# UNG8077_EVB_7801-9031_A_4-KSZ9031.net
KiCad netlist of a schematic drawn in Altium Designer
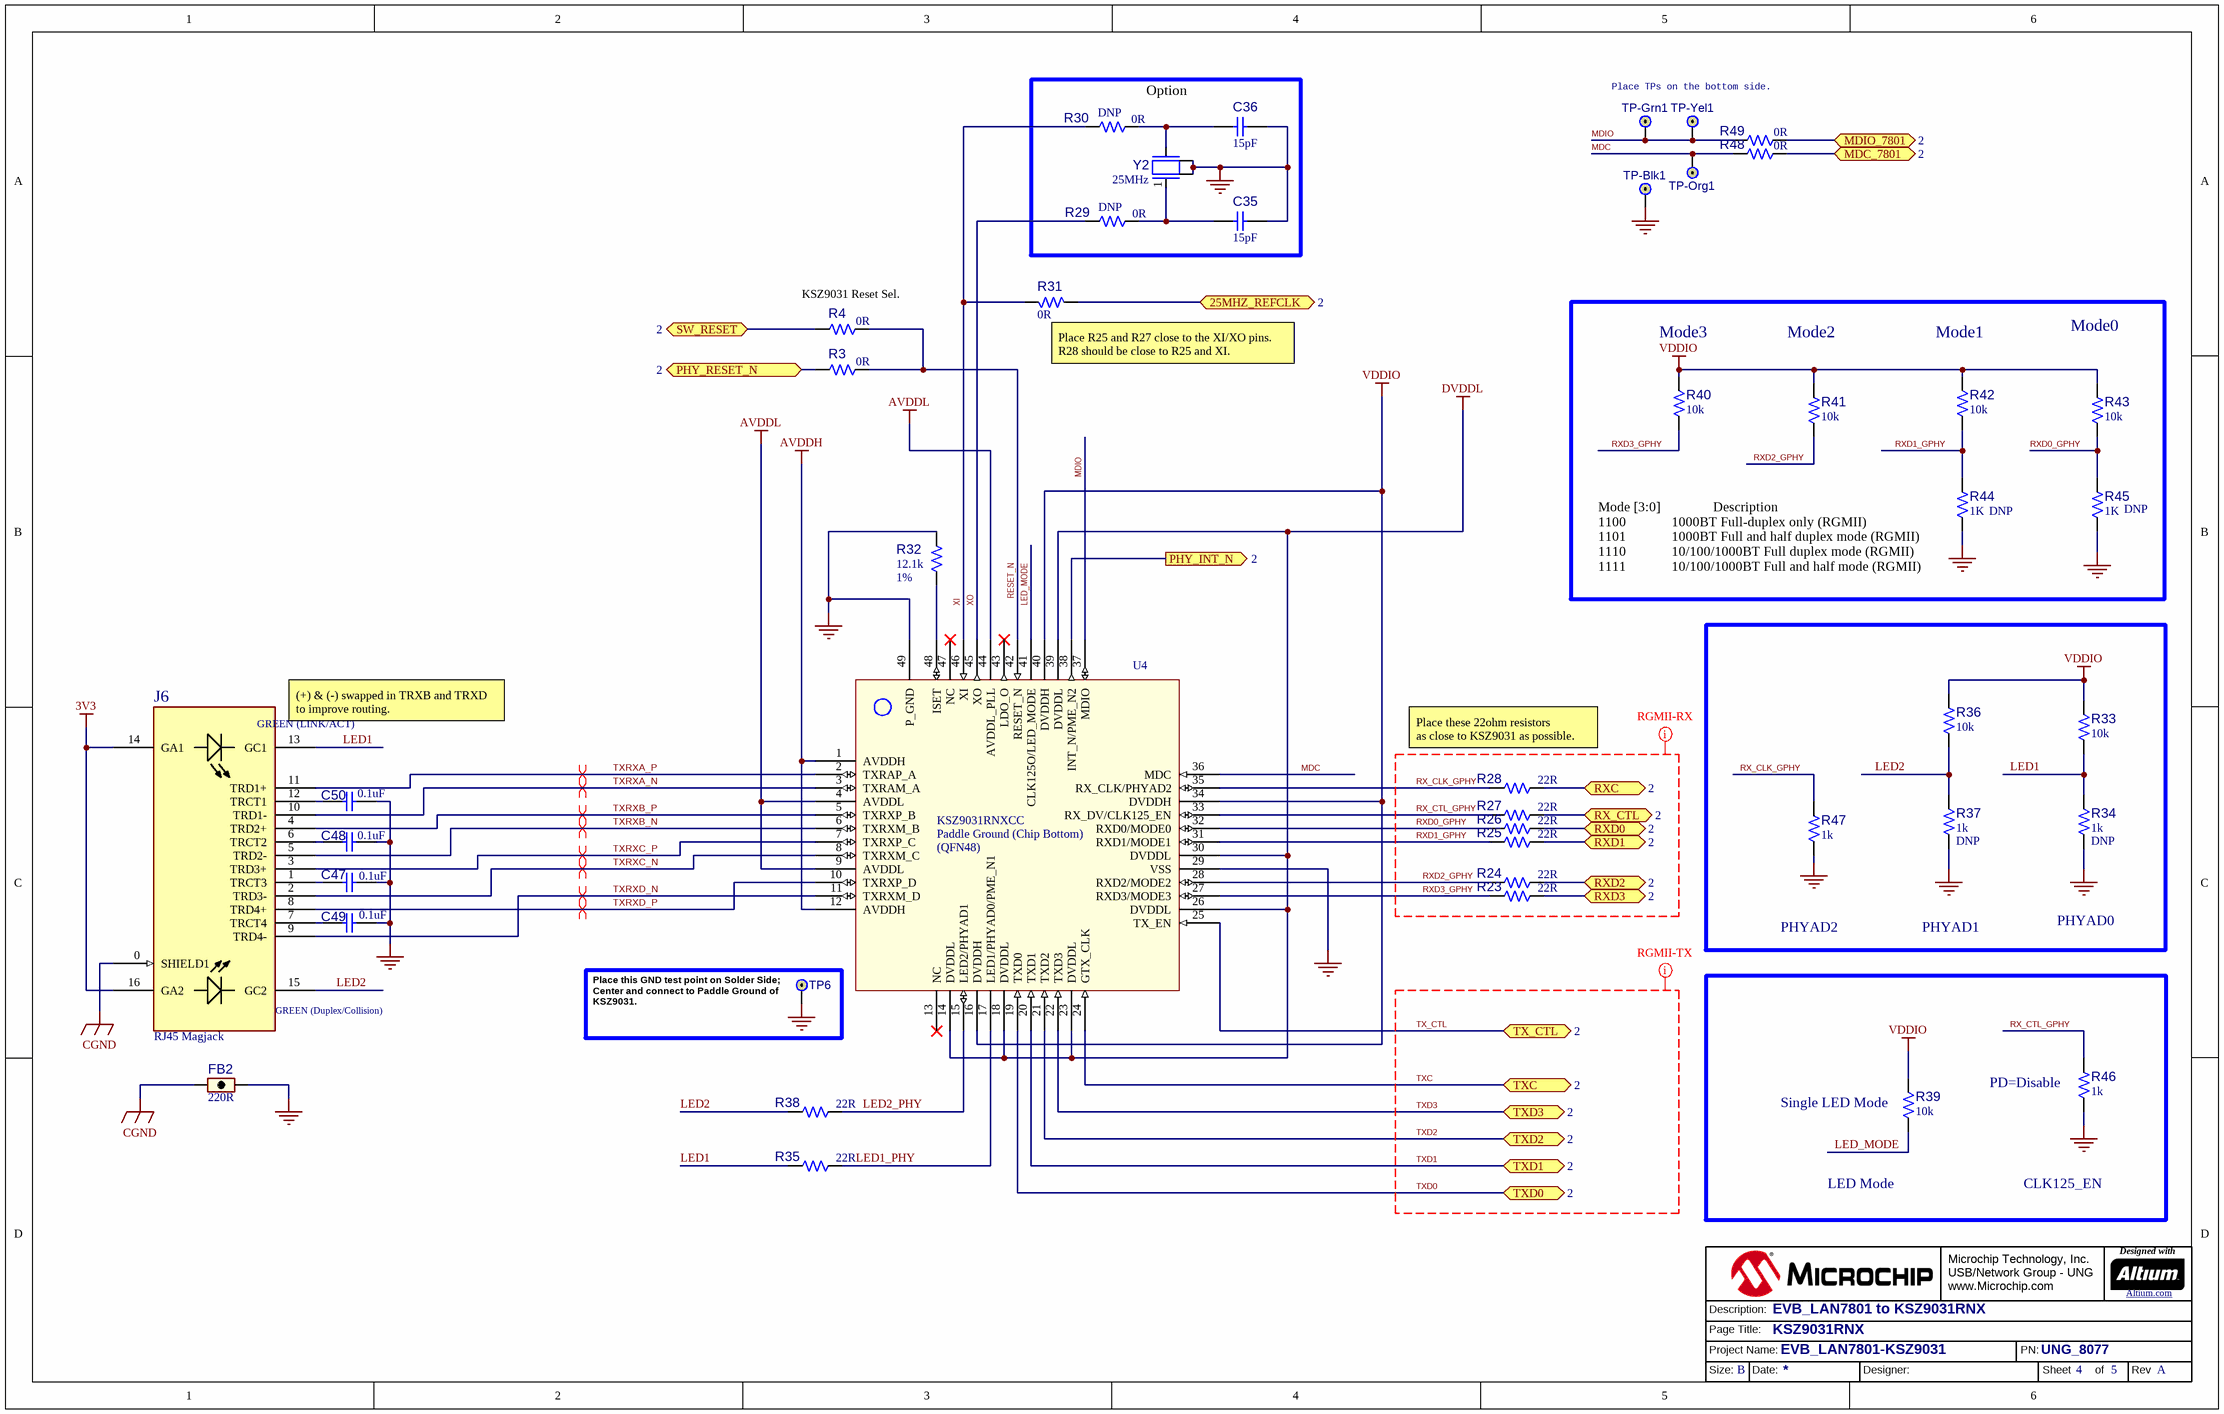
[diagram p0: UNG8077_EVB_7801-9031_A_4-KSZ9031.SchDoc]

(export (version "E")
  (design (tool "Eeschema 10.0.6"))
  (components
    (comp (ref "C35")
      (value "15pF")
      (footprint "CAP_C_0402")
      (description "Capacitor")
      (fields
        (field (name "TOLERANCE") "5%")
        (field (name "Comment") "Capacitor NP")
        (field (name "OWNER") "Gabor Bihari")
      )
      (libsource (lib "MCHP-CDB-Offline") (part "Capacitor NP"))
    )
    (comp (ref "C36")
      (value "15pF")
      (footprint "CAP_C_0402")
      (description "Capacitor")
      (fields
        (field (name "TOLERANCE") "5%")
        (field (name "Comment") "Capacitor NP")
        (field (name "OWNER") "Gabor Bihari")
      )
      (libsource (lib "MCHP-CDB-Offline") (part "Capacitor NP"))
    )
    (comp (ref "C47")
      (value "0.1uF")
      (footprint "CAP_C_0402")
      (description "Capacitor")
      (fields
        (field (name "TOLERANCE") "10%")
        (field (name "Comment") "CAP CER 0.1UF 35V")
        (field (name "OWNER") "Jamus Griego")
      )
      (libsource (lib "MCHP-CDB-Offline") (part "Capacitor NP"))
    )
    (comp (ref "C48")
      (value "0.1uF")
      (footprint "CAP_C_0402")
      (description "Capacitor")
      (fields
        (field (name "TOLERANCE") "10%")
        (field (name "Comment") "CAP CER 0.1UF 35V")
        (field (name "OWNER") "Jamus Griego")
      )
      (libsource (lib "MCHP-CDB-Offline") (part "Capacitor NP"))
    )
    (comp (ref "C49")
      (value "0.1uF")
      (footprint "CAP_C_0402")
      (description "Capacitor")
      (fields
        (field (name "TOLERANCE") "10%")
        (field (name "Comment") "CAP CER 0.1UF 35V")
        (field (name "OWNER") "Jamus Griego")
      )
      (libsource (lib "MCHP-CDB-Offline") (part "Capacitor NP"))
    )
    (comp (ref "C50")
      (value "0.1uF")
      (footprint "CAP_C_0402")
      (description "Capacitor")
      (fields
        (field (name "TOLERANCE") "10%")
        (field (name "Comment") "CAP CER 0.1UF 35V")
        (field (name "OWNER") "Jamus Griego")
      )
      (libsource (lib "MCHP-CDB-Offline") (part "Capacitor NP"))
    )
    (comp (ref "FB2")
      (value "220R")
      (footprint "IND_C_0603")
      (fields (field (name "Comment") "Ferrite Bead") (field (name "OWNER") "Razvan Cristescu"))
      (libsource (lib "MCHP-CDB-Offline") (part "Ferrite Bead"))
    )
    (comp (ref "J6")
      (value "RJ45 Magjack")
      (footprint "CON_MODULAR_RJ45_TH_RA_RJMG2012211A0FR")
      (description "CON RJ-45 RJMG2012211A0FR")
      (libsource (lib "UNG_CONNECTORS") (part "CON RJ-45 RJMG2012211A0FR"))
    )
    (comp (ref "R3")
      (value "0R")
      (footprint "RES_C_0603")
      (description "Resistor")
      (fields (field (name "POWER") "1/10W"))
      (libsource (lib "MCHP-CDB-Offline") (part "Resistor"))
    )
    (comp (ref "R4")
      (value "0R")
      (footprint "RES_C_0603")
      (description "Resistor")
      (fields (field (name "POWER") "1/10W"))
      (libsource (lib "MCHP-CDB-Offline") (part "Resistor"))
    )
    (comp (ref "R23")
      (value "22R")
      (footprint "RES_C_0402")
      (description "Resistor")
      (fields
        (field (name "TOLERANCE") "1%")
        (field (name "POWER") "1/10W")
        (field (name "OWNER") "Mike Ragsdale")
      )
      (libsource (lib "MCHP-CDB") (part "Resistor"))
    )
    (comp (ref "R24")
      (value "22R")
      (footprint "RES_C_0402")
      (description "Resistor")
      (fields
        (field (name "TOLERANCE") "1%")
        (field (name "POWER") "1/10W")
        (field (name "OWNER") "Mike Ragsdale")
      )
      (libsource (lib "MCHP-CDB") (part "Resistor"))
    )
    (comp (ref "R25")
      (value "22R")
      (footprint "RES_C_0402")
      (description "Resistor")
      (fields
        (field (name "TOLERANCE") "1%")
        (field (name "POWER") "1/10W")
        (field (name "OWNER") "Mike Ragsdale")
      )
      (libsource (lib "MCHP-CDB") (part "Resistor"))
    )
    (comp (ref "R26")
      (value "22R")
      (footprint "RES_C_0402")
      (description "Resistor")
      (fields
        (field (name "TOLERANCE") "1%")
        (field (name "POWER") "1/10W")
        (field (name "OWNER") "Mike Ragsdale")
      )
      (libsource (lib "MCHP-CDB") (part "Resistor"))
    )
    (comp (ref "R27")
      (value "22R")
      (footprint "RES_C_0402")
      (description "Resistor")
      (fields
        (field (name "TOLERANCE") "1%")
        (field (name "POWER") "1/10W")
        (field (name "OWNER") "Mike Ragsdale")
      )
      (libsource (lib "MCHP-CDB") (part "Resistor"))
    )
    (comp (ref "R28")
      (value "22R")
      (footprint "RES_C_0402")
      (description "Resistor")
      (fields
        (field (name "TOLERANCE") "1%")
        (field (name "POWER") "1/10W")
        (field (name "OWNER") "Mike Ragsdale")
      )
      (libsource (lib "MCHP-CDB") (part "Resistor"))
    )
    (comp (ref "R29")
      (value "0R")
      (footprint "RES_C_0603")
      (description "Resistor")
      (fields (field (name "POWER") "1/10W") (field (name "POPULATED") "DNP"))
      (libsource (lib "MCHP-CDB-Offline") (part "Resistor"))
    )
    (comp (ref "R30")
      (value "0R")
      (footprint "RES_C_0603")
      (description "Resistor")
      (fields (field (name "POWER") "1/10W") (field (name "POPULATED") "DNP"))
      (libsource (lib "MCHP-CDB-Offline") (part "Resistor"))
    )
    (comp (ref "R31")
      (value "0R")
      (footprint "RES_C_0603")
      (description "Resistor")
      (fields (field (name "POWER") "1/10W"))
      (libsource (lib "MCHP-CDB-Offline") (part "Resistor"))
    )
    (comp (ref "R32")
      (value "12.1k")
      (footprint "RES_C_0603")
      (description "Resistor")
      (fields (field (name "TOLERANCE") "1%") (field (name "VOLTAGE") "75V") (field (name "POWER") "1/10W"))
      (libsource (lib "MCHP-CDB-Offline") (part "Resistor"))
    )
    (comp (ref "R33")
      (value "10k")
      (footprint "RES_C_0603")
      (description "Resistor")
      (fields (field (name "VOLTAGE") "75V") (field (name "POWER") "1/10W"))
      (libsource (lib "MCHP-CDB-Offline") (part "Resistor"))
    )
    (comp (ref "R34")
      (value "1k")
      (footprint "RES_C_0603")
      (description "Resistor")
      (fields (field (name "TOLERANCE") "1%") (field (name "VOLTAGE") "75V") (field (name "POPULATED") "DNP"))
      (libsource (lib "MCHP-CDB") (part "Resistor"))
    )
    (comp (ref "R35")
      (value "22R")
      (footprint "RES_C_0402")
      (description "Resistor")
      (fields
        (field (name "TOLERANCE") "1%")
        (field (name "POWER") "1/10W")
        (field (name "OWNER") "Mike Ragsdale")
      )
      (libsource (lib "MCHP-CDB") (part "Resistor"))
    )
    (comp (ref "R36")
      (value "10k")
      (footprint "RES_C_0603")
      (description "Resistor")
      (fields (field (name "VOLTAGE") "75V") (field (name "POWER") "1/10W"))
      (libsource (lib "MCHP-CDB-Offline") (part "Resistor"))
    )
    (comp (ref "R37")
      (value "1k")
      (footprint "RES_C_0603")
      (description "Resistor")
      (fields (field (name "TOLERANCE") "1%") (field (name "VOLTAGE") "75V") (field (name "POPULATED") "DNP"))
      (libsource (lib "MCHP-CDB") (part "Resistor"))
    )
    (comp (ref "R38")
      (value "22R")
      (footprint "RES_C_0402")
      (description "Resistor")
      (fields
        (field (name "TOLERANCE") "1%")
        (field (name "POWER") "1/10W")
        (field (name "OWNER") "Mike Ragsdale")
      )
      (libsource (lib "MCHP-CDB") (part "Resistor"))
    )
    (comp (ref "R39")
      (value "10k")
      (footprint "RES_C_0603")
      (description "Resistor")
      (fields (field (name "VOLTAGE") "75V") (field (name "POWER") "1/10W"))
      (libsource (lib "MCHP-CDB-Offline") (part "Resistor"))
    )
    (comp (ref "R40")
      (value "10k")
      (footprint "RES_C_0603")
      (description "Resistor")
      (fields (field (name "VOLTAGE") "75V") (field (name "POWER") "1/10W"))
      (libsource (lib "MCHP-CDB-Offline") (part "Resistor"))
    )
    (comp (ref "R41")
      (value "10k")
      (footprint "RES_C_0603")
      (description "Resistor")
      (fields (field (name "VOLTAGE") "75V") (field (name "POWER") "1/10W"))
      (libsource (lib "MCHP-CDB-Offline") (part "Resistor"))
    )
    (comp (ref "R42")
      (value "10k")
      (footprint "RES_C_0603")
      (description "Resistor")
      (fields (field (name "VOLTAGE") "75V") (field (name "POWER") "1/10W"))
      (libsource (lib "MCHP-CDB-Offline") (part "Resistor"))
    )
    (comp (ref "R43")
      (value "10k")
      (footprint "RES_C_0603")
      (description "Resistor")
      (fields (field (name "VOLTAGE") "75V") (field (name "POWER") "1/10W"))
      (libsource (lib "MCHP-CDB-Offline") (part "Resistor"))
    )
    (comp (ref "R44")
      (value "1K")
      (footprint "RES_C_0603")
      (description "Resistor")
      (fields (field (name "TOLERANCE") "5%") (field (name "VOLTAGE") "75V") (field (name "POPULATED") "DNP"))
      (libsource (lib "MCHP-CDB-Offline") (part "Resistor"))
    )
    (comp (ref "R45")
      (value "1K")
      (footprint "RES_C_0603")
      (description "Resistor")
      (fields (field (name "TOLERANCE") "5%") (field (name "VOLTAGE") "75V") (field (name "POPULATED") "DNP"))
      (libsource (lib "MCHP-CDB-Offline") (part "Resistor"))
    )
    (comp (ref "R46")
      (value "1k")
      (footprint "RES_C_0603")
      (description "Resistor")
      (fields (field (name "TOLERANCE") "1%") (field (name "VOLTAGE") "75V"))
      (libsource (lib "MCHP-CDB") (part "Resistor"))
    )
    (comp (ref "R47")
      (value "1k")
      (footprint "RES_C_0603")
      (description "Resistor")
      (fields (field (name "TOLERANCE") "1%") (field (name "VOLTAGE") "75V"))
      (libsource (lib "MCHP-CDB") (part "Resistor"))
    )
    (comp (ref "R48")
      (value "0R")
      (footprint "RES_C_0603")
      (description "Resistor")
      (fields (field (name "POWER") "1/10W"))
      (libsource (lib "MCHP-CDB-Offline") (part "Resistor"))
    )
    (comp (ref "R49")
      (value "0R")
      (footprint "RES_C_0603")
      (description "Resistor")
      (fields (field (name "POWER") "1/10W"))
      (libsource (lib "MCHP-CDB-Offline") (part "Resistor"))
    )
    (comp (ref "TP-Blk1")
      (value "Jumper")
      (footprint "TP_PAD51D36")
      (description "Test Pad TH 51X36")
      (fields (field (name "MANUFACTURER PART NUMBER") "none"))
      (libsource (lib "UNG_CONNECTORS") (part "TEST PAD TH 51X36"))
    )
    (comp (ref "TP-Grn1")
      (value "Jumper")
      (footprint "TP_PAD51D36")
      (description "Test Pad TH 51X36")
      (fields (field (name "MANUFACTURER PART NUMBER") "none"))
      (libsource (lib "UNG_CONNECTORS") (part "TEST PAD TH 51X36"))
    )
    (comp (ref "TP-Org1")
      (value "Jumper")
      (footprint "TP_PAD51D36")
      (description "Test Pad TH 51X36")
      (fields (field (name "MANUFACTURER PART NUMBER") "none"))
      (libsource (lib "UNG_CONNECTORS") (part "TEST PAD TH 51X36"))
    )
    (comp (ref "TP-Yel1")
      (value "Jumper")
      (footprint "TP_PAD51D36")
      (description "Test Pad TH 51X36")
      (fields (field (name "MANUFACTURER PART NUMBER") "none"))
      (libsource (lib "UNG_CONNECTORS") (part "TEST PAD TH 51X36"))
    )
    (comp (ref "TP6")
      (value "Jumper")
      (footprint "TP_PAD_VIA_20-10")
      (description "Test Pad TH VIA 20X10")
      (fields (field (name "MANUFACTURER PART NUMBER") "none"))
      (libsource (lib "UNG_CONNECTORS") (part "TEST PAD TH VIA 20X10"))
    )
    (comp (ref "U4")
      (value "~")
      (footprint "QFN-48_7x7-EP5.1sq")
      (description "KSZ9031RNXCC 10/100/100 GPHY with RGMII 48QFN")
      (fields
        (field (name "OWNER") "Jennifer Hancock")
        (field (name "PART CHECKED") "Jennifer Hancock")
        (field (name "PART FOOTPRINT CHECKED") "Carl Johnson")
      )
      (libsource (lib "UNG_UNG") (part "KSZ9031RNXCC"))
    )
    (comp (ref "Y2")
      (value "XTAL 25MHz 4 pins 3225")
      (footprint "XTAL_4PIN_3M2X2M5")
      (description "Crystal 25MHz 4 pins 3225")
      (fields (field (name "FREQUENCY") "25MHz"))
      (libsource (lib "UNG_XTAL_OSC") (part "XTAL 25MHz 4 pins 3225"))
    )
  )
  (nets
    (net (code "1") (name "/25MHZ_REFCLK") (class "Default")
      (node (ref "R31") (pin "1") (pinfunction "1_1") (pintype "passive"))
    )
    (net (code "2") (name "/LED1") (class "Default")
      (node (ref "J6") (pin "13") (pinfunction "GC1_13") (pintype "passive"))
      (node (ref "R33") (pin "2") (pinfunction "2_2") (pintype "passive"))
      (node (ref "R34") (pin "2") (pinfunction "2_2") (pintype "passive"))
      (node (ref "R35") (pin "1") (pinfunction "1_1") (pintype "passive"))
    )
    (net (code "3") (name "/LED1_PHY") (class "Default")
      (node (ref "R35") (pin "2") (pinfunction "2_2") (pintype "passive"))
      (node (ref "U4") (pin "17") (pinfunction "LED1/PHYAD0/PME_N1_17") (pintype "passive"))
    )
    (net (code "4") (name "/LED2") (class "Default")
      (node (ref "J6") (pin "15") (pinfunction "GC2_15") (pintype "passive"))
      (node (ref "R36") (pin "2") (pinfunction "2_2") (pintype "passive"))
      (node (ref "R37") (pin "2") (pinfunction "2_2") (pintype "passive"))
      (node (ref "R38") (pin "1") (pinfunction "1_1") (pintype "passive"))
    )
    (net (code "5") (name "/LED2_PHY") (class "Default")
      (node (ref "R38") (pin "2") (pinfunction "2_2") (pintype "passive"))
      (node (ref "U4") (pin "15") (pinfunction "LED2/PHYAD1_15") (pintype "bidirectional"))
    )
    (net (code "6") (name "/LED_MODE") (class "Default")
      (node (ref "R39") (pin "2") (pinfunction "2_2") (pintype "passive"))
      (node (ref "U4") (pin "41") (pinfunction "CLK125O/LED_MODE_41") (pintype "passive"))
    )
    (net (code "7") (name "/MDC") (class "Default")
      (node (ref "R48") (pin "1") (pinfunction "1_1") (pintype "passive"))
      (node (ref "TP-Org1") (pin "1") (pinfunction "P1_1") (pintype "passive"))
      (node (ref "U4") (pin "36") (pinfunction "MDC_36") (pintype "input"))
    )
    (net (code "8") (name "/MDC_7801") (class "Default")
      (node (ref "R48") (pin "2") (pinfunction "2_2") (pintype "passive"))
    )
    (net (code "9") (name "/MDIO") (class "Default")
      (node (ref "R49") (pin "1") (pinfunction "1_1") (pintype "passive"))
      (node (ref "TP-Grn1") (pin "1") (pinfunction "P1_1") (pintype "passive"))
      (node (ref "TP-Yel1") (pin "1") (pinfunction "P1_1") (pintype "passive"))
      (node (ref "U4") (pin "37") (pinfunction "MDIO_37") (pintype "bidirectional"))
    )
    (net (code "10") (name "/MDIO_7801") (class "Default")
      (node (ref "R49") (pin "2") (pinfunction "2_2") (pintype "passive"))
    )
    (net (code "11") (name "/PHY_INT_N") (class "Default")
      (node (ref "U4") (pin "38") (pinfunction "INT_N/PME_N2_38") (pintype "output"))
    )
    (net (code "12") (name "/PHY_RESET_N") (class "Default")
      (node (ref "R3") (pin "1") (pinfunction "1_1") (pintype "passive"))
    )
    (net (code "13") (name "/RESET_N") (class "Default")
      (node (ref "R3") (pin "2") (pinfunction "2_2") (pintype "passive"))
      (node (ref "R4") (pin "2") (pinfunction "2_2") (pintype "passive"))
      (node (ref "U4") (pin "42") (pinfunction "RESET_N_42") (pintype "input"))
    )
    (net (code "14") (name "/RXC") (class "Default")
      (node (ref "R28") (pin "2") (pinfunction "2_2") (pintype "passive"))
    )
    (net (code "15") (name "/RXD0") (class "Default")
      (node (ref "R26") (pin "2") (pinfunction "2_2") (pintype "passive"))
    )
    (net (code "16") (name "/RXD0_GPHY") (class "Default")
      (node (ref "R26") (pin "1") (pinfunction "1_1") (pintype "passive"))
      (node (ref "R43") (pin "2") (pinfunction "2_2") (pintype "passive"))
      (node (ref "R45") (pin "2") (pinfunction "2_2") (pintype "passive"))
      (node (ref "U4") (pin "32") (pinfunction "RXD0/MODE0_32") (pintype "bidirectional"))
    )
    (net (code "17") (name "/RXD1") (class "Default")
      (node (ref "R25") (pin "2") (pinfunction "2_2") (pintype "passive"))
    )
    (net (code "18") (name "/RXD1_GPHY") (class "Default")
      (node (ref "R25") (pin "1") (pinfunction "1_1") (pintype "passive"))
      (node (ref "R42") (pin "2") (pinfunction "2_2") (pintype "passive"))
      (node (ref "R44") (pin "2") (pinfunction "2_2") (pintype "passive"))
      (node (ref "U4") (pin "31") (pinfunction "RXD1/MODE1_31") (pintype "bidirectional"))
    )
    (net (code "19") (name "/RXD2") (class "Default")
      (node (ref "R24") (pin "2") (pinfunction "2_2") (pintype "passive"))
    )
    (net (code "20") (name "/RXD2_GPHY") (class "Default")
      (node (ref "R24") (pin "1") (pinfunction "1_1") (pintype "passive"))
      (node (ref "R41") (pin "2") (pinfunction "2_2") (pintype "passive"))
      (node (ref "U4") (pin "28") (pinfunction "RXD2/MODE2_28") (pintype "bidirectional"))
    )
    (net (code "21") (name "/RXD3") (class "Default")
      (node (ref "R23") (pin "2") (pinfunction "2_2") (pintype "passive"))
    )
    (net (code "22") (name "/RXD3_GPHY") (class "Default")
      (node (ref "R23") (pin "1") (pinfunction "1_1") (pintype "passive"))
      (node (ref "R40") (pin "2") (pinfunction "2_2") (pintype "passive"))
      (node (ref "U4") (pin "27") (pinfunction "RXD3/MODE3_27") (pintype "bidirectional"))
    )
    (net (code "23") (name "/RX_CLK_GPHY") (class "Default")
      (node (ref "R28") (pin "1") (pinfunction "1_1") (pintype "passive"))
      (node (ref "R47") (pin "2") (pinfunction "2_2") (pintype "passive"))
      (node (ref "U4") (pin "35") (pinfunction "RX_CLK/PHYAD2_35") (pintype "bidirectional"))
    )
    (net (code "24") (name "/RX_CTL") (class "Default")
      (node (ref "R27") (pin "2") (pinfunction "2_2") (pintype "passive"))
    )
    (net (code "25") (name "/RX_CTL_GPHY") (class "Default")
      (node (ref "R27") (pin "1") (pinfunction "1_1") (pintype "passive"))
      (node (ref "R46") (pin "2") (pinfunction "2_2") (pintype "passive"))
      (node (ref "U4") (pin "33") (pinfunction "RX_DV/CLK125_EN_33") (pintype "bidirectional"))
    )
    (net (code "26") (name "/SW_RESET") (class "Default")
      (node (ref "R4") (pin "1") (pinfunction "1_1") (pintype "passive"))
    )
    (net (code "27") (name "/TXC") (class "Default")
      (node (ref "U4") (pin "24") (pinfunction "GTX_CLK_24") (pintype "input"))
    )
    (net (code "28") (name "/TXD0") (class "Default")
      (node (ref "U4") (pin "19") (pinfunction "TXD0_19") (pintype "input"))
    )
    (net (code "29") (name "/TXD1") (class "Default")
      (node (ref "U4") (pin "20") (pinfunction "TXD1_20") (pintype "input"))
    )
    (net (code "30") (name "/TXD2") (class "Default")
      (node (ref "U4") (pin "21") (pinfunction "TXD2_21") (pintype "input"))
    )
    (net (code "31") (name "/TXD3") (class "Default")
      (node (ref "U4") (pin "22") (pinfunction "TXD3_22") (pintype "input"))
    )
    (net (code "32") (name "/TXRXA_N") (class "Default")
      (node (ref "J6") (pin "10") (pinfunction "TRD1-_10") (pintype "passive"))
      (node (ref "U4") (pin "3") (pinfunction "TXRAM_A_3") (pintype "bidirectional"))
    )
    (net (code "33") (name "/TXRXA_P") (class "Default")
      (node (ref "J6") (pin "11") (pinfunction "TRD1+_11") (pintype "passive"))
      (node (ref "U4") (pin "2") (pinfunction "TXRAP_A_2") (pintype "bidirectional"))
    )
    (net (code "34") (name "/TXRXB_N") (class "Default")
      (node (ref "J6") (pin "5") (pinfunction "TRD2-_5") (pintype "passive"))
      (node (ref "U4") (pin "6") (pinfunction "TXRXM_B_6") (pintype "bidirectional"))
    )
    (net (code "35") (name "/TXRXB_P") (class "Default")
      (node (ref "J6") (pin "4") (pinfunction "TRD2+_4") (pintype "passive"))
      (node (ref "U4") (pin "5") (pinfunction "TXRXP_B_5") (pintype "bidirectional"))
    )
    (net (code "36") (name "/TXRXC_N") (class "Default")
      (node (ref "J6") (pin "2") (pinfunction "TRD3-_2") (pintype "passive"))
      (node (ref "U4") (pin "8") (pinfunction "TXRXM_C_8") (pintype "bidirectional"))
    )
    (net (code "37") (name "/TXRXC_P") (class "Default")
      (node (ref "J6") (pin "3") (pinfunction "TRD3+_3") (pintype "passive"))
      (node (ref "U4") (pin "7") (pinfunction "TXRXP_C_7") (pintype "bidirectional"))
    )
    (net (code "38") (name "/TXRXD_N") (class "Default")
      (node (ref "J6") (pin "9") (pinfunction "TRD4-_9") (pintype "passive"))
      (node (ref "U4") (pin "11") (pinfunction "TXRXM_D_11") (pintype "bidirectional"))
    )
    (net (code "39") (name "/TXRXD_P") (class "Default")
      (node (ref "J6") (pin "8") (pinfunction "TRD4+_8") (pintype "passive"))
      (node (ref "U4") (pin "10") (pinfunction "TXRXP_D_10") (pintype "bidirectional"))
    )
    (net (code "40") (name "/TX_CTL") (class "Default")
      (node (ref "U4") (pin "25") (pinfunction "TX_EN_25") (pintype "input"))
    )
    (net (code "41") (name "/XI") (class "Default")
      (node (ref "R30") (pin "1") (pinfunction "1_1") (pintype "passive"))
      (node (ref "R31") (pin "2") (pinfunction "2_2") (pintype "passive"))
      (node (ref "U4") (pin "46") (pinfunction "XI_46") (pintype "input"))
    )
    (net (code "42") (name "/XO") (class "Default")
      (node (ref "R29") (pin "1") (pinfunction "1_1") (pintype "passive"))
      (node (ref "U4") (pin "45") (pinfunction "XO_45") (pintype "output"))
    )
    (net (code "43") (name "3V3") (class "Default")
      (node (ref "J6") (pin "14") (pinfunction "GA1_14") (pintype "passive"))
      (node (ref "J6") (pin "16") (pinfunction "GA2_16") (pintype "passive"))
    )
    (net (code "44") (name "AVDDH") (class "Default")
      (node (ref "U4") (pin "1") (pinfunction "AVDDH_1") (pintype "power_in"))
      (node (ref "U4") (pin "12") (pinfunction "AVDDH_12") (pintype "power_in"))
    )
    (net (code "45") (name "AVDDL") (class "Default")
      (node (ref "U4") (pin "4") (pinfunction "AVDDL_4") (pintype "power_in"))
      (node (ref "U4") (pin "44") (pinfunction "AVDDL_PLL_44") (pintype "power_in"))
      (node (ref "U4") (pin "9") (pinfunction "AVDDL_9") (pintype "power_in"))
    )
    (net (code "46") (name "CGND") (class "Default")
      (node (ref "FB2") (pin "1") (pinfunction "1_1") (pintype "passive"))
      (node (ref "J6") (pin "0") (pinfunction "SHIELD1_0") (pintype "input"))
    )
    (net (code "47") (name "DVDDL") (class "Default")
      (node (ref "U4") (pin "14") (pinfunction "DVDDL_14") (pintype "power_in"))
      (node (ref "U4") (pin "18") (pinfunction "DVDDL_18") (pintype "power_in"))
      (node (ref "U4") (pin "23") (pinfunction "DVDDL_23") (pintype "power_in"))
      (node (ref "U4") (pin "26") (pinfunction "DVDDL_26") (pintype "power_in"))
      (node (ref "U4") (pin "30") (pinfunction "DVDDL_30") (pintype "power_in"))
      (node (ref "U4") (pin "39") (pinfunction "DVDDL_39") (pintype "power_in"))
    )
    (net (code "48") (name "GND") (class "Default")
      (node (ref "C35") (pin "2") (pinfunction "2_2") (pintype "passive"))
      (node (ref "C36") (pin "2") (pinfunction "2_2") (pintype "passive"))
      (node (ref "C47") (pin "2") (pinfunction "2_2") (pintype "passive"))
      (node (ref "C48") (pin "2") (pinfunction "2_2") (pintype "passive"))
      (node (ref "C49") (pin "2") (pinfunction "2_2") (pintype "passive"))
      (node (ref "C50") (pin "2") (pinfunction "2_2") (pintype "passive"))
      (node (ref "FB2") (pin "2") (pinfunction "2_2") (pintype "passive"))
      (node (ref "R32") (pin "2") (pinfunction "2_2") (pintype "passive"))
      (node (ref "R34") (pin "1") (pinfunction "1_1") (pintype "passive"))
      (node (ref "R37") (pin "1") (pinfunction "1_1") (pintype "passive"))
      (node (ref "R44") (pin "1") (pinfunction "1_1") (pintype "passive"))
      (node (ref "R45") (pin "1") (pinfunction "1_1") (pintype "passive"))
      (node (ref "R46") (pin "1") (pinfunction "1_1") (pintype "passive"))
      (node (ref "R47") (pin "1") (pinfunction "1_1") (pintype "passive"))
      (node (ref "TP-Blk1") (pin "1") (pinfunction "P1_1") (pintype "passive"))
      (node (ref "TP6") (pin "1") (pinfunction "P1_1") (pintype "passive"))
      (node (ref "U4") (pin "29") (pinfunction "VSS_29") (pintype "passive"))
      (node (ref "U4") (pin "49") (pinfunction "P_GND_49") (pintype "passive"))
      (node (ref "Y2") (pin "2") (pinfunction "GND_2") (pintype "power_in"))
      (node (ref "Y2") (pin "4") (pinfunction "GND_4") (pintype "power_in"))
    )
    (net (code "49") (name "Net-(J6-TRCT1)") (class "Default")
      (node (ref "C50") (pin "1") (pinfunction "1_1") (pintype "passive"))
      (node (ref "J6") (pin "12") (pinfunction "TRCT1_12") (pintype "passive"))
    )
    (net (code "50") (name "Net-(J6-TRCT2)") (class "Default")
      (node (ref "C48") (pin "1") (pinfunction "1_1") (pintype "passive"))
      (node (ref "J6") (pin "6") (pinfunction "TRCT2_6") (pintype "passive"))
    )
    (net (code "51") (name "Net-(J6-TRCT3)") (class "Default")
      (node (ref "C47") (pin "1") (pinfunction "1_1") (pintype "passive"))
      (node (ref "J6") (pin "1") (pinfunction "TRCT3_1") (pintype "passive"))
    )
    (net (code "52") (name "Net-(J6-TRCT4)") (class "Default")
      (node (ref "C49") (pin "1") (pinfunction "1_1") (pintype "passive"))
      (node (ref "J6") (pin "7") (pinfunction "TRCT4_7") (pintype "passive"))
    )
    (net (code "53") (name "Net-(U4-ISET)") (class "Default")
      (node (ref "R32") (pin "1") (pinfunction "1_1") (pintype "passive"))
      (node (ref "U4") (pin "48") (pinfunction "ISET_48") (pintype "bidirectional"))
    )
    (net (code "54") (name "Net-(Y2-Osc1)") (class "Default")
      (node (ref "C35") (pin "1") (pinfunction "1_1") (pintype "passive"))
      (node (ref "R29") (pin "2") (pinfunction "2_2") (pintype "passive"))
      (node (ref "Y2") (pin "1") (pinfunction "Osc1_1") (pintype "passive"))
    )
    (net (code "55") (name "Net-(Y2-Osc2)") (class "Default")
      (node (ref "C36") (pin "1") (pinfunction "1_1") (pintype "passive"))
      (node (ref "R30") (pin "2") (pinfunction "2_2") (pintype "passive"))
      (node (ref "Y2") (pin "3") (pinfunction "Osc2_3") (pintype "passive"))
    )
    (net (code "56") (name "VDDIO") (class "Default")
      (node (ref "R33") (pin "1") (pinfunction "1_1") (pintype "passive"))
      (node (ref "R36") (pin "1") (pinfunction "1_1") (pintype "passive"))
      (node (ref "R39") (pin "1") (pinfunction "1_1") (pintype "passive"))
      (node (ref "R40") (pin "1") (pinfunction "1_1") (pintype "passive"))
      (node (ref "R41") (pin "1") (pinfunction "1_1") (pintype "passive"))
      (node (ref "R42") (pin "1") (pinfunction "1_1") (pintype "passive"))
      (node (ref "R43") (pin "1") (pinfunction "1_1") (pintype "passive"))
      (node (ref "U4") (pin "16") (pinfunction "DVDDH_16") (pintype "power_in"))
      (node (ref "U4") (pin "34") (pinfunction "DVDDH_34") (pintype "power_in"))
      (node (ref "U4") (pin "40") (pinfunction "DVDDH_40") (pintype "power_in"))
    )
    (net (code "57") (name "unconnected-(U4-LDO_O-Pad43)") (class "Default")
      (node (ref "U4") (pin "43") (pinfunction "LDO_O_43") (pintype "output+no_connect"))
    )
    (net (code "58") (name "unconnected-(U4-NC-Pad13)") (class "Default")
      (node (ref "U4") (pin "13") (pinfunction "NC_13") (pintype "passive+no_connect"))
    )
    (net (code "59") (name "unconnected-(U4-NC-Pad47)") (class "Default")
      (node (ref "U4") (pin "47") (pinfunction "NC_47") (pintype "passive+no_connect"))
    )
  )
)
